# CANtranslator.net
KiCad netlist of a schematic drawn in EAGLE
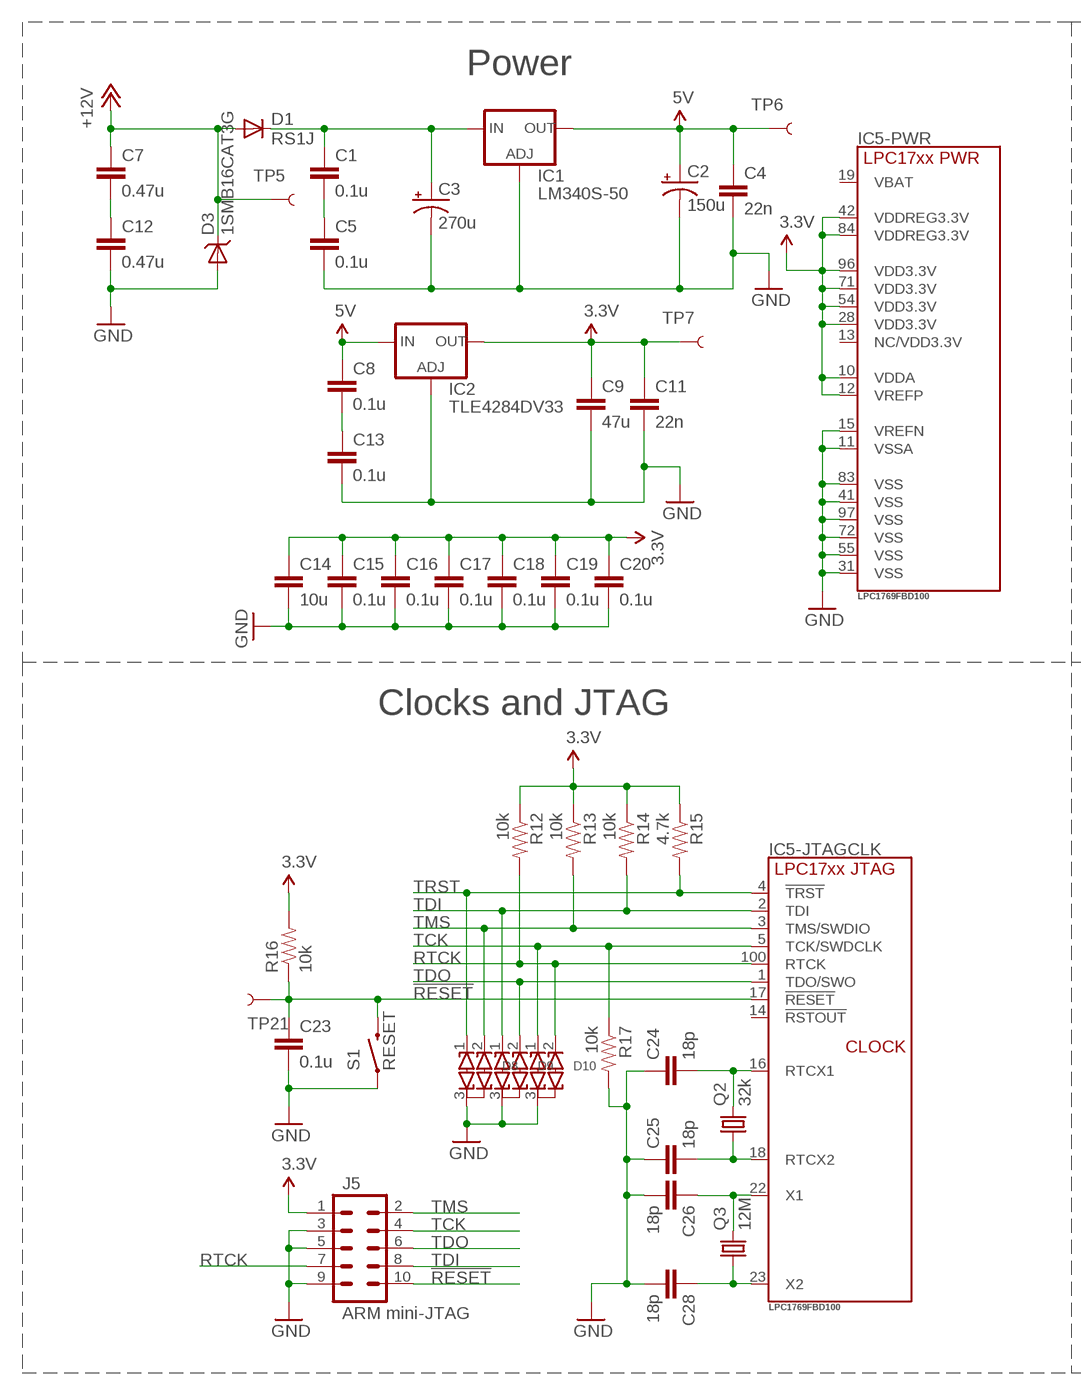
[diagram p0: schematic, sheet 1, part 1 of 2]
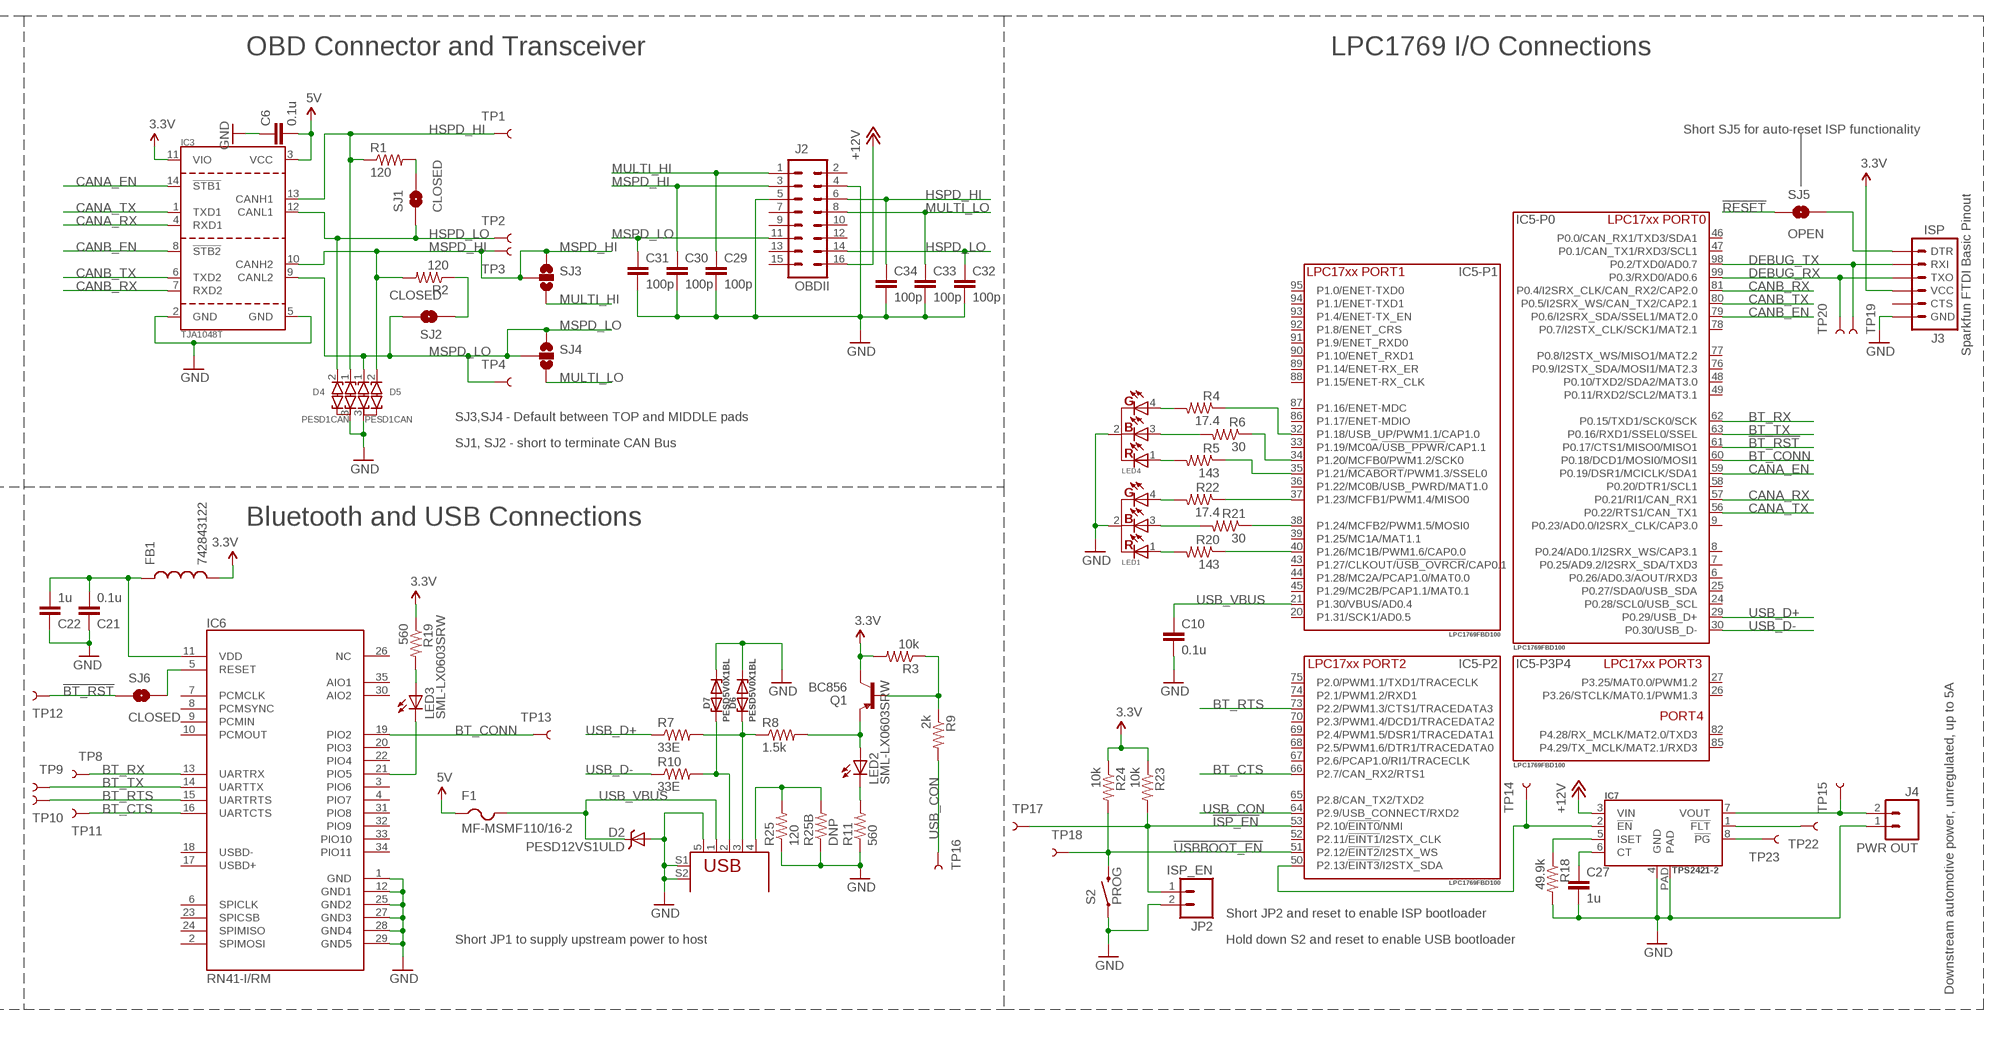
[diagram p1: schematic, sheet 1, part 2 of 2]

(export (version "E")
  (design (tool "Eeschema 10.0.6"))
  (components
    (comp (ref "C1")
      (value "0.1u")
      (footprint "eagle-import:0805")
      (libsource (lib "eagle-import") (part "CAP0805"))
    )
    (comp (ref "C2")
      (value "150u")
      (footprint "eagle-import:CPOL-5MMX2D")
      (libsource (lib "eagle-import") (part "CAP_POL5MMX2D"))
    )
    (comp (ref "C3")
      (value "270u")
      (footprint "eagle-import:CPOL-10MMX5D")
      (libsource (lib "eagle-import") (part "CAP_POL10MMX5D"))
    )
    (comp (ref "C4")
      (value "22n")
      (footprint "eagle-import:0402-CAP")
      (libsource (lib "eagle-import") (part "CAP0402-CAP"))
    )
    (comp (ref "C5")
      (value "0.1u")
      (footprint "eagle-import:0805")
      (libsource (lib "eagle-import") (part "CAP0805"))
    )
    (comp (ref "C6")
      (value "0.1u")
      (footprint "eagle-import:0402-CAP")
      (libsource (lib "eagle-import") (part "CAP0402-CAP"))
    )
    (comp (ref "C7")
      (value "0.47u")
      (footprint "eagle-import:0805")
      (libsource (lib "eagle-import") (part "CAP0805"))
    )
    (comp (ref "C8")
      (value "0.1u")
      (footprint "eagle-import:0805")
      (libsource (lib "eagle-import") (part "CAP0805"))
    )
    (comp (ref "C9")
      (value "47u")
      (footprint "eagle-import:1210")
      (libsource (lib "eagle-import") (part "CAP1210"))
    )
    (comp (ref "C10")
      (value "0.1u")
      (footprint "eagle-import:0402-CAP")
      (libsource (lib "eagle-import") (part "CAP0402-CAP"))
    )
    (comp (ref "C11")
      (value "22n")
      (footprint "eagle-import:0402-CAP")
      (libsource (lib "eagle-import") (part "CAP0402-CAP"))
    )
    (comp (ref "C12")
      (value "0.47u")
      (footprint "eagle-import:0805")
      (libsource (lib "eagle-import") (part "CAP0805"))
    )
    (comp (ref "C13")
      (value "0.1u")
      (footprint "eagle-import:0805")
      (libsource (lib "eagle-import") (part "CAP0805"))
    )
    (comp (ref "C14")
      (value "10u")
      (footprint "eagle-import:0805")
      (libsource (lib "eagle-import") (part "CAP0805"))
    )
    (comp (ref "C15")
      (value "0.1u")
      (footprint "eagle-import:0402-CAP")
      (libsource (lib "eagle-import") (part "CAP0402-CAP"))
    )
    (comp (ref "C16")
      (value "0.1u")
      (footprint "eagle-import:0402-CAP")
      (libsource (lib "eagle-import") (part "CAP0402-CAP"))
    )
    (comp (ref "C17")
      (value "0.1u")
      (footprint "eagle-import:0402-CAP")
      (libsource (lib "eagle-import") (part "CAP0402-CAP"))
    )
    (comp (ref "C18")
      (value "0.1u")
      (footprint "eagle-import:0402-CAP")
      (libsource (lib "eagle-import") (part "CAP0402-CAP"))
    )
    (comp (ref "C19")
      (value "0.1u")
      (footprint "eagle-import:0402-CAP")
      (libsource (lib "eagle-import") (part "CAP0402-CAP"))
    )
    (comp (ref "C20")
      (value "0.1u")
      (footprint "eagle-import:0402-CAP")
      (libsource (lib "eagle-import") (part "CAP0402-CAP"))
    )
    (comp (ref "C21")
      (value "0.1u")
      (footprint "eagle-import:0402-CAP")
      (libsource (lib "eagle-import") (part "CAP0402-CAP"))
    )
    (comp (ref "C22")
      (value "1u")
      (footprint "eagle-import:0402-CAP")
      (libsource (lib "eagle-import") (part "CAP0402-CAP"))
    )
    (comp (ref "C23")
      (value "0.1u")
      (footprint "eagle-import:0402-CAP")
      (libsource (lib "eagle-import") (part "CAP0402-CAP"))
    )
    (comp (ref "C24")
      (value "18p")
      (footprint "eagle-import:0402-CAP")
      (libsource (lib "eagle-import") (part "CAP0402-CAP"))
    )
    (comp (ref "C25")
      (value "18p")
      (footprint "eagle-import:0402-CAP")
      (libsource (lib "eagle-import") (part "CAP0402-CAP"))
    )
    (comp (ref "C26")
      (value "18p")
      (footprint "eagle-import:0402-CAP")
      (libsource (lib "eagle-import") (part "CAP0402-CAP"))
    )
    (comp (ref "C27")
      (value "1u")
      (footprint "eagle-import:0402-CAP")
      (libsource (lib "eagle-import") (part "CAP0402-CAP"))
    )
    (comp (ref "C28")
      (value "18p")
      (footprint "eagle-import:0402-CAP")
      (libsource (lib "eagle-import") (part "CAP0402-CAP"))
    )
    (comp (ref "C29")
      (value "100p")
      (footprint "eagle-import:0402-CAP")
      (libsource (lib "eagle-import") (part "CAP0402-CAP"))
    )
    (comp (ref "C30")
      (value "100p")
      (footprint "eagle-import:0402-CAP")
      (libsource (lib "eagle-import") (part "CAP0402-CAP"))
    )
    (comp (ref "C31")
      (value "100p")
      (footprint "eagle-import:0402-CAP")
      (libsource (lib "eagle-import") (part "CAP0402-CAP"))
    )
    (comp (ref "C32")
      (value "100p")
      (footprint "eagle-import:0402-CAP")
      (libsource (lib "eagle-import") (part "CAP0402-CAP"))
    )
    (comp (ref "C33")
      (value "100p")
      (footprint "eagle-import:0402-CAP")
      (libsource (lib "eagle-import") (part "CAP0402-CAP"))
    )
    (comp (ref "C34")
      (value "100p")
      (footprint "eagle-import:0402-CAP")
      (libsource (lib "eagle-import") (part "CAP0402-CAP"))
    )
    (comp (ref "D1")
      (value "RS1J")
      (footprint "eagle-import:SMA-DIODE")
      (libsource (lib "eagle-import") (part "DIODESMA"))
    )
    (comp (ref "D2")
      (value "PESD12VS1ULD")
      (footprint "eagle-import:SOD-882D")
      (libsource (lib "eagle-import") (part "DIODE-TVS-SOD882D"))
    )
    (comp (ref "D3")
      (value "1SMB16CAT3G")
      (footprint "eagle-import:SMB-DIODE")
      (libsource (lib "eagle-import") (part "DIODE-TVS-SMB"))
    )
    (comp (ref "D4")
      (value "PESD1CAN")
      (footprint "eagle-import:SOT23")
      (libsource (lib "eagle-import") (part "DIODE_ESD_DUAL-SOT-23"))
    )
    (comp (ref "D5")
      (value "PESD1CAN")
      (footprint "eagle-import:SOT23")
      (libsource (lib "eagle-import") (part "DIODE_ESD_DUAL-SOT-23"))
    )
    (comp (ref "D6")
      (value "PESD5V0X1BL")
      (footprint "eagle-import:SOD-882")
      (libsource (lib "eagle-import") (part "DIODE_ESD_BI-SOD882"))
    )
    (comp (ref "D7")
      (value "PESD5V0X1BL")
      (footprint "eagle-import:SOD-882")
      (libsource (lib "eagle-import") (part "DIODE_ESD_BI-SOD882"))
    )
    (comp (ref "D8")
      (value "DIODE_ESD_DUAL-SOT-1123")
      (footprint "eagle-import:SOT-1123")
      (libsource (lib "eagle-import") (part "DIODE_ESD_DUAL-SOT-1123"))
    )
    (comp (ref "D9")
      (value "DIODE_ESD_DUAL-SOT-1123")
      (footprint "eagle-import:SOT-1123")
      (libsource (lib "eagle-import") (part "DIODE_ESD_DUAL-SOT-1123"))
    )
    (comp (ref "D10")
      (value "DIODE_ESD_DUAL-SOT-1123")
      (footprint "eagle-import:SOT-1123")
      (libsource (lib "eagle-import") (part "DIODE_ESD_DUAL-SOT-1123"))
    )
    (comp (ref "F1")
      (value "MF-MSMF110/16-2")
      (footprint "eagle-import:R1206")
      (libsource (lib "eagle-import") (part "PTCFUSE-1206"))
    )
    (comp (ref "FB1")
      (value "742843122")
      (footprint "eagle-import:C0402")
      (libsource (lib "eagle-import") (part "INDUCTOR0402"))
    )
    (comp (ref "IC1")
      (value "LM340S-50")
      (footprint "eagle-import:V-REG_DPACK")
      (libsource (lib "eagle-import") (part "V_REG_317DPACK"))
    )
    (comp (ref "IC2")
      (value "TLE4284DV33")
      (footprint "eagle-import:V-REG_DPACK")
      (libsource (lib "eagle-import") (part "V_REG_317DPACK"))
    )
    (comp (ref "IC3")
      (value "TJA1048T")
      (footprint "eagle-import:SO14")
      (libsource (lib "eagle-import") (part "TJA1048-SO14"))
    )
    (comp (ref "IC5")
      (value "LPC1769FBD100")
      (footprint "eagle-import:TQFP100")
      (libsource (lib "eagle-import") (part "LPC1768_SPLIT-TQFP"))
    )
    (comp (ref "IC6")
      (value "RN41-I/RM")
      (footprint "eagle-import:RN41")
      (libsource (lib "eagle-import") (part "BLUETOOTH-RN41{dblquote}"))
    )
    (comp (ref "IC7")
      (value "TPS2421-2")
      (footprint "eagle-import:POWER_SO8")
      (libsource (lib "eagle-import") (part "TPS2421SO8"))
    )
    (comp (ref "J1")
      (value "USB_MINIB_SHIELD-10118193")
      (footprint "eagle-import:10118193")
      (libsource (lib "eagle-import") (part "USB_MINIB_SHIELD-10118193"))
    )
    (comp (ref "J2")
      (value "OBDII")
      (footprint "eagle-import:OBDII-COMTECH")
      (libsource (lib "eagle-import") (part "M08X2-OBDII-COMTECH"))
    )
    (comp (ref "J3")
      (value "ISP")
      (footprint "eagle-import:1X06")
      (libsource (lib "eagle-import") (part "ARDUINO_SERIAL_PROGRAMPTH"))
    )
    (comp (ref "J4")
      (value "PWR OUT")
      (footprint "eagle-import:2-1445055-2")
      (libsource (lib "eagle-import") (part "M022-1445055-2"))
    )
    (comp (ref "J5")
      (value "ARM mini-JTAG")
      (footprint "eagle-import:SHF-105-01-X-D-SM")
      (libsource (lib "eagle-import") (part "M05X2-SHF-105-01-X-D-SM"))
    )
    (comp (ref "JP2")
      (value "ISP_EN")
      (footprint "eagle-import:1X02")
      (libsource (lib "eagle-import") (part "SparkFun-Connectors_M02PTH"))
    )
    (comp (ref "LED1")
      (value "RGB")
      (footprint "eagle-import:LED5MM-RGB")
      (libsource (lib "eagle-import") (part "LED_3X_COMMON_CATHODE"))
    )
    (comp (ref "LED2")
      (value "SML-LX0603SRW")
      (footprint "eagle-import:LED-0603")
      (libsource (lib "eagle-import") (part "LED0603"))
    )
    (comp (ref "LED3")
      (value "SML-LX0603SRW")
      (footprint "eagle-import:LED-0603")
      (libsource (lib "eagle-import") (part "LED0603"))
    )
    (comp (ref "LED4")
      (value "RGB")
      (footprint "eagle-import:LED5MM-RGB")
      (libsource (lib "eagle-import") (part "LED_3X_COMMON_CATHODE"))
    )
    (comp (ref "Q1")
      (value "BC856")
      (footprint "eagle-import:SOT23-3")
      (libsource (lib "eagle-import") (part "TRANSISTOR_PNPSMD"))
    )
    (comp (ref "Q2")
      (value "32k")
      (footprint "eagle-import:ST2012SB")
      (libsource (lib "eagle-import") (part "CRYSTAL-ST2012SB"))
    )
    (comp (ref "Q3")
      (value "12M")
      (footprint "eagle-import:CX3225SB")
      (libsource (lib "eagle-import") (part "CRYSTAL-CX3225SB"))
    )
    (comp (ref "R1")
      (value "120")
      (footprint "eagle-import:0402-RES")
      (libsource (lib "eagle-import") (part "RESISTOR0402-RES"))
    )
    (comp (ref "R2")
      (value "120")
      (footprint "eagle-import:0402-RES")
      (libsource (lib "eagle-import") (part "RESISTOR0402-RES"))
    )
    (comp (ref "R3")
      (value "10k")
      (footprint "eagle-import:0402-RES")
      (libsource (lib "eagle-import") (part "RESISTOR0402-RES"))
    )
    (comp (ref "R4")
      (value "17.4")
      (footprint "eagle-import:0402-RES")
      (libsource (lib "eagle-import") (part "RESISTOR0402-RES"))
    )
    (comp (ref "R5")
      (value "143")
      (footprint "eagle-import:0402-RES")
      (libsource (lib "eagle-import") (part "RESISTOR0402-RES"))
    )
    (comp (ref "R6")
      (value "30")
      (footprint "eagle-import:0402-RES")
      (libsource (lib "eagle-import") (part "RESISTOR0402-RES"))
    )
    (comp (ref "R7")
      (value "33E")
      (footprint "eagle-import:0402-RES")
      (libsource (lib "eagle-import") (part "RESISTOR0402-RES"))
    )
    (comp (ref "R8")
      (value "1.5k")
      (footprint "eagle-import:0402-RES")
      (libsource (lib "eagle-import") (part "RESISTOR0402-RES"))
    )
    (comp (ref "R9")
      (value "2k")
      (footprint "eagle-import:0402-RES")
      (libsource (lib "eagle-import") (part "RESISTOR0402-RES"))
    )
    (comp (ref "R10")
      (value "33E")
      (footprint "eagle-import:0402-RES")
      (libsource (lib "eagle-import") (part "RESISTOR0402-RES"))
    )
    (comp (ref "R11")
      (value "560")
      (footprint "eagle-import:0402-RES")
      (libsource (lib "eagle-import") (part "RESISTOR0402-RES"))
    )
    (comp (ref "R12")
      (value "10k")
      (footprint "eagle-import:0402-RES")
      (libsource (lib "eagle-import") (part "RESISTOR0402-RES"))
    )
    (comp (ref "R13")
      (value "10k")
      (footprint "eagle-import:0402-RES")
      (libsource (lib "eagle-import") (part "RESISTOR0402-RES"))
    )
    (comp (ref "R14")
      (value "10k")
      (footprint "eagle-import:0402-RES")
      (libsource (lib "eagle-import") (part "RESISTOR0402-RES"))
    )
    (comp (ref "R15")
      (value "4.7k")
      (footprint "eagle-import:0402-RES")
      (libsource (lib "eagle-import") (part "RESISTOR0402-RES"))
    )
    (comp (ref "R16")
      (value "10k")
      (footprint "eagle-import:0402-RES")
      (libsource (lib "eagle-import") (part "RESISTOR0402-RES"))
    )
    (comp (ref "R17")
      (value "10k")
      (footprint "eagle-import:0402-RES")
      (libsource (lib "eagle-import") (part "RESISTOR0402-RES"))
    )
    (comp (ref "R18")
      (value "49.9k")
      (footprint "eagle-import:0402-RES")
      (libsource (lib "eagle-import") (part "RESISTOR0402-RES"))
    )
    (comp (ref "R19")
      (value "560")
      (footprint "eagle-import:0402-RES")
      (libsource (lib "eagle-import") (part "RESISTOR0402-RES"))
    )
    (comp (ref "R20")
      (value "143")
      (footprint "eagle-import:0402-RES")
      (libsource (lib "eagle-import") (part "RESISTOR0402-RES"))
    )
    (comp (ref "R21")
      (value "30")
      (footprint "eagle-import:0402-RES")
      (libsource (lib "eagle-import") (part "RESISTOR0402-RES"))
    )
    (comp (ref "R22")
      (value "17.4")
      (footprint "eagle-import:0402-RES")
      (libsource (lib "eagle-import") (part "RESISTOR0402-RES"))
    )
    (comp (ref "R23")
      (value "10k")
      (footprint "eagle-import:0402-RES")
      (libsource (lib "eagle-import") (part "RESISTOR0402-RES"))
    )
    (comp (ref "R24")
      (value "10k")
      (footprint "eagle-import:0402-RES")
      (libsource (lib "eagle-import") (part "RESISTOR0402-RES"))
    )
    (comp (ref "R25")
      (value "120")
      (footprint "eagle-import:0402-RES")
      (libsource (lib "eagle-import") (part "RESISTOR0402-RES"))
    )
    (comp (ref "R25B")
      (value "DNP")
      (footprint "eagle-import:AXIAL-0.4")
      (libsource (lib "eagle-import") (part "RESISTORPTH-1/4W"))
    )
    (comp (ref "S1")
      (value "RESET")
      (footprint "eagle-import:TACTILE-SWITCH-1101NE")
      (libsource (lib "eagle-import") (part "SWITCH-MOMENTARY-2-SMD-1101NE"))
    )
    (comp (ref "S2")
      (value "PROG")
      (footprint "eagle-import:TACTILE-SWITCH-1101NE")
      (libsource (lib "eagle-import") (part "SWITCH-MOMENTARY-2-SMD-1101NE"))
    )
    (comp (ref "SJ1")
      (value "CLOSED")
      (footprint "eagle-import:SJ_2S-TRACE")
      (libsource (lib "eagle-import") (part "SOLDERJUMPERTRACE"))
    )
    (comp (ref "SJ2")
      (value "CLOSED")
      (footprint "eagle-import:SJ_2S-TRACE")
      (libsource (lib "eagle-import") (part "SOLDERJUMPERTRACE"))
    )
    (comp (ref "SJ3")
      (value "SOLDERJUMPER_2WAYPASTE1&2")
      (footprint "eagle-import:SJ_3_PASTE1&2")
      (libsource (lib "eagle-import") (part "SOLDERJUMPER_2WAYPASTE1&2"))
    )
    (comp (ref "SJ4")
      (value "SOLDERJUMPER_2WAYPASTE1&2")
      (footprint "eagle-import:SJ_3_PASTE1&2")
      (libsource (lib "eagle-import") (part "SOLDERJUMPER_2WAYPASTE1&2"))
    )
    (comp (ref "SJ5")
      (value "OPEN")
      (footprint "eagle-import:SJ_2S-NO")
      (libsource (lib "eagle-import") (part "SOLDERJUMPERNO"))
    )
    (comp (ref "SJ6")
      (value "CLOSED")
      (footprint "eagle-import:SJ_2S-TRACE")
      (libsource (lib "eagle-import") (part "SOLDERJUMPERTRACE"))
    )
    (comp (ref "TP1")
      (value "TEST-POINT3X5")
      (footprint "eagle-import:PAD.03X.05")
      (libsource (lib "eagle-import") (part "TEST-POINT3X5"))
    )
    (comp (ref "TP2")
      (value "TEST-POINT3X5")
      (footprint "eagle-import:PAD.03X.05")
      (libsource (lib "eagle-import") (part "TEST-POINT3X5"))
    )
    (comp (ref "TP3")
      (value "TEST-POINT3X5")
      (footprint "eagle-import:PAD.03X.05")
      (libsource (lib "eagle-import") (part "TEST-POINT3X5"))
    )
    (comp (ref "TP4")
      (value "TEST-POINT3X5")
      (footprint "eagle-import:PAD.03X.05")
      (libsource (lib "eagle-import") (part "TEST-POINT3X5"))
    )
    (comp (ref "TP5")
      (value "TEST-POINT3X5")
      (footprint "eagle-import:PAD.03X.05")
      (libsource (lib "eagle-import") (part "TEST-POINT3X5"))
    )
    (comp (ref "TP6")
      (value "TEST-POINT3X5")
      (footprint "eagle-import:PAD.03X.05")
      (libsource (lib "eagle-import") (part "TEST-POINT3X5"))
    )
    (comp (ref "TP7")
      (value "TEST-POINT3X5")
      (footprint "eagle-import:PAD.03X.05")
      (libsource (lib "eagle-import") (part "TEST-POINT3X5"))
    )
    (comp (ref "TP8")
      (value "TEST-POINT3X5")
      (footprint "eagle-import:PAD.03X.05")
      (libsource (lib "eagle-import") (part "TEST-POINT3X5"))
    )
    (comp (ref "TP9")
      (value "TEST-POINT3X5")
      (footprint "eagle-import:PAD.03X.05")
      (libsource (lib "eagle-import") (part "TEST-POINT3X5"))
    )
    (comp (ref "TP10")
      (value "TEST-POINT3X5")
      (footprint "eagle-import:PAD.03X.05")
      (libsource (lib "eagle-import") (part "TEST-POINT3X5"))
    )
    (comp (ref "TP11")
      (value "TEST-POINT3X5")
      (footprint "eagle-import:PAD.03X.05")
      (libsource (lib "eagle-import") (part "TEST-POINT3X5"))
    )
    (comp (ref "TP12")
      (value "TEST-POINT3X5")
      (footprint "eagle-import:PAD.03X.05")
      (libsource (lib "eagle-import") (part "TEST-POINT3X5"))
    )
    (comp (ref "TP13")
      (value "TEST-POINT3X5")
      (footprint "eagle-import:PAD.03X.05")
      (libsource (lib "eagle-import") (part "TEST-POINT3X5"))
    )
    (comp (ref "TP14")
      (value "TEST-POINT3X5")
      (footprint "eagle-import:PAD.03X.05")
      (libsource (lib "eagle-import") (part "TEST-POINT3X5"))
    )
    (comp (ref "TP15")
      (value "TEST-POINT3X5")
      (footprint "eagle-import:PAD.03X.05")
      (libsource (lib "eagle-import") (part "TEST-POINT3X5"))
    )
    (comp (ref "TP16")
      (value "TEST-POINT3X5")
      (footprint "eagle-import:PAD.03X.05")
      (libsource (lib "eagle-import") (part "TEST-POINT3X5"))
    )
    (comp (ref "TP17")
      (value "TEST-POINT3X5")
      (footprint "eagle-import:PAD.03X.05")
      (libsource (lib "eagle-import") (part "TEST-POINT3X5"))
    )
    (comp (ref "TP18")
      (value "TEST-POINT3X5")
      (footprint "eagle-import:PAD.03X.05")
      (libsource (lib "eagle-import") (part "TEST-POINT3X5"))
    )
    (comp (ref "TP19")
      (value "TEST-POINT3X5")
      (footprint "eagle-import:PAD.03X.05")
      (libsource (lib "eagle-import") (part "TEST-POINT3X5"))
    )
    (comp (ref "TP20")
      (value "TEST-POINT3X5")
      (footprint "eagle-import:PAD.03X.05")
      (libsource (lib "eagle-import") (part "TEST-POINT3X5"))
    )
    (comp (ref "TP21")
      (value "TEST-POINT3X5")
      (footprint "eagle-import:PAD.03X.05")
      (libsource (lib "eagle-import") (part "TEST-POINT3X5"))
    )
    (comp (ref "TP22")
      (value "TEST-POINT3X5")
      (footprint "eagle-import:PAD.03X.05")
      (libsource (lib "eagle-import") (part "TEST-POINT3X5"))
    )
    (comp (ref "TP23")
      (value "TEST-POINT3X5")
      (footprint "eagle-import:PAD.03X.05")
      (libsource (lib "eagle-import") (part "TEST-POINT3X5"))
    )
  )
  (nets
    (net (code "1") (name "+12V") (class "Default")
      (node (ref "C7") (pin "1") (pinfunction "1_1") (pintype "passive"))
      (node (ref "D1") (pin "A") (pinfunction "A_A") (pintype "passive"))
      (node (ref "D3") (pin "C") (pinfunction "C_C") (pintype "passive"))
      (node (ref "IC7") (pin "3") (pinfunction "VIN_3") (pintype "bidirectional"))
      (node (ref "J2") (pin "16") (pinfunction "16_16") (pintype "passive"))
      (node (ref "TP5") (pin "P$1") (pinfunction "1_P$1") (pintype "bidirectional"))
    )
    (net (code "2") (name "/BT_CONN") (class "Default")
      (node (ref "IC5") (pin "60") (pinfunction "P0.18/DCD1/MOSI0/MOSI1_60") (pintype "bidirectional"))
      (node (ref "IC6") (pin "19") (pinfunction "PIO2_19") (pintype "bidirectional"))
      (node (ref "TP13") (pin "P$1") (pinfunction "1_P$1") (pintype "bidirectional"))
    )
    (net (code "3") (name "/BT_CTS") (class "Default")
      (node (ref "IC5") (pin "66") (pinfunction "P2.7/CAN_RX2/RTS1_66") (pintype "bidirectional"))
      (node (ref "IC6") (pin "16") (pinfunction "UARTCTS_16") (pintype "bidirectional"))
      (node (ref "TP11") (pin "P$1") (pinfunction "1_P$1") (pintype "bidirectional"))
    )
    (net (code "4") (name "/BT_RTS") (class "Default")
      (node (ref "IC5") (pin "73") (pinfunction "P2.2/PWM1.3/CTS1/TRACEDATA3_73") (pintype "bidirectional"))
      (node (ref "IC6") (pin "15") (pinfunction "UARTRTS_15") (pintype "bidirectional"))
      (node (ref "TP10") (pin "P$1") (pinfunction "1_P$1") (pintype "bidirectional"))
    )
    (net (code "5") (name "/BT_RX") (class "Default")
      (node (ref "IC5") (pin "62") (pinfunction "P0.15/TXD1/SCK0/SCK_62") (pintype "bidirectional"))
      (node (ref "IC6") (pin "13") (pinfunction "UARTRX_13") (pintype "bidirectional"))
      (node (ref "TP8") (pin "P$1") (pinfunction "1_P$1") (pintype "bidirectional"))
    )
    (net (code "6") (name "/BT_TX") (class "Default")
      (node (ref "IC5") (pin "63") (pinfunction "P0.16/RXD1/SSEL0/SSEL_63") (pintype "bidirectional"))
      (node (ref "IC6") (pin "14") (pinfunction "UARTTX_14") (pintype "bidirectional"))
      (node (ref "TP9") (pin "P$1") (pinfunction "1_P$1") (pintype "bidirectional"))
    )
    (net (code "7") (name "/CANA_EN") (class "Default")
      (node (ref "IC3") (pin "14") (pinfunction "~{STB1}_14") (pintype "bidirectional"))
      (node (ref "IC5") (pin "59") (pinfunction "P0.19/DSR1/MCICLK/SDA1_59") (pintype "bidirectional"))
    )
    (net (code "8") (name "/CANA_RX") (class "Default")
      (node (ref "IC3") (pin "4") (pinfunction "RXD1_4") (pintype "bidirectional"))
      (node (ref "IC5") (pin "57") (pinfunction "P0.21/RI1/CAN_RX1_57") (pintype "bidirectional"))
    )
    (net (code "9") (name "/CANA_TX") (class "Default")
      (node (ref "IC3") (pin "1") (pinfunction "TXD1_1") (pintype "bidirectional"))
      (node (ref "IC5") (pin "56") (pinfunction "P0.22/RTS1/CAN_TX1_56") (pintype "bidirectional"))
    )
    (net (code "10") (name "/CANB_EN") (class "Default")
      (node (ref "IC3") (pin "8") (pinfunction "~{STB2}_8") (pintype "bidirectional"))
      (node (ref "IC5") (pin "79") (pinfunction "P0.6/I2SRX_SDA/SSEL1/MAT2.0_79") (pintype "bidirectional"))
    )
    (net (code "11") (name "/CANB_RX") (class "Default")
      (node (ref "IC3") (pin "7") (pinfunction "RXD2_7") (pintype "bidirectional"))
      (node (ref "IC5") (pin "81") (pinfunction "P0.4/I2SRX_CLK/CAN_RX2/CAP2.0_81") (pintype "bidirectional"))
    )
    (net (code "12") (name "/CANB_TX") (class "Default")
      (node (ref "IC3") (pin "6") (pinfunction "TXD2_6") (pintype "bidirectional"))
      (node (ref "IC5") (pin "80") (pinfunction "P0.5/I2SRX_WS/CAN_TX2/CAP2.1_80") (pintype "bidirectional"))
    )
    (net (code "13") (name "/DEBUG_RX") (class "Default")
      (node (ref "IC5") (pin "99") (pinfunction "P0.3/RXD0/AD0.6_99") (pintype "bidirectional"))
      (node (ref "J3") (pin "3") (pinfunction "TXO_3") (pintype "passive"))
      (node (ref "TP20") (pin "P$1") (pinfunction "1_P$1") (pintype "bidirectional"))
    )
    (net (code "14") (name "/DEBUG_TX") (class "Default")
      (node (ref "IC5") (pin "98") (pinfunction "P0.2/TXD0/AD0.7_98") (pintype "bidirectional"))
      (node (ref "J3") (pin "2") (pinfunction "RXI_2") (pintype "passive"))
      (node (ref "TP19") (pin "P$1") (pinfunction "1_P$1") (pintype "bidirectional"))
    )
    (net (code "15") (name "/HSPD_HI") (class "Default")
      (node (ref "C34") (pin "1") (pinfunction "1_1") (pintype "passive"))
      (node (ref "D4") (pin "1") (pinfunction "C1_1") (pintype "power_in"))
      (node (ref "IC3") (pin "13") (pinfunction "CANH1_13") (pintype "bidirectional"))
      (node (ref "J2") (pin "6") (pinfunction "6_6") (pintype "passive"))
      (node (ref "R1") (pin "1") (pinfunction "1_1") (pintype "passive"))
      (node (ref "TP1") (pin "P$1") (pinfunction "1_P$1") (pintype "bidirectional"))
    )
    (net (code "16") (name "/HSPD_LO") (class "Default")
      (node (ref "C32") (pin "1") (pinfunction "1_1") (pintype "passive"))
      (node (ref "D4") (pin "2") (pinfunction "C2_2") (pintype "power_in"))
      (node (ref "IC3") (pin "12") (pinfunction "CANL1_12") (pintype "bidirectional"))
      (node (ref "J2") (pin "14") (pinfunction "14_14") (pintype "passive"))
      (node (ref "SJ1") (pin "1") (pinfunction "1_1") (pintype "passive"))
      (node (ref "TP2") (pin "P$1") (pinfunction "1_P$1") (pintype "bidirectional"))
    )
    (net (code "17") (name "/MSPD_HI") (class "Default")
      (node (ref "C30") (pin "1") (pinfunction "1_1") (pintype "passive"))
      (node (ref "D5") (pin "2") (pinfunction "C2_2") (pintype "power_in"))
      (node (ref "IC3") (pin "10") (pinfunction "CANH2_10") (pintype "bidirectional"))
      (node (ref "J2") (pin "3") (pinfunction "3_3") (pintype "passive"))
      (node (ref "R2") (pin "2") (pinfunction "2_2") (pintype "passive"))
      (node (ref "SJ3") (pin "1") (pinfunction "1_1") (pintype "passive"))
      (node (ref "SJ3") (pin "2") (pinfunction "2_2") (pintype "passive"))
      (node (ref "TP3") (pin "P$1") (pinfunction "1_P$1") (pintype "bidirectional"))
    )
    (net (code "18") (name "/MSPD_LO") (class "Default")
      (node (ref "C31") (pin "1") (pinfunction "1_1") (pintype "passive"))
      (node (ref "D5") (pin "1") (pinfunction "C1_1") (pintype "power_in"))
      (node (ref "IC3") (pin "9") (pinfunction "CANL2_9") (pintype "bidirectional"))
      (node (ref "J2") (pin "11") (pinfunction "11_11") (pintype "passive"))
      (node (ref "SJ2") (pin "2") (pinfunction "2_2") (pintype "passive"))
      (node (ref "SJ4") (pin "1") (pinfunction "1_1") (pintype "passive"))
      (node (ref "SJ4") (pin "2") (pinfunction "2_2") (pintype "passive"))
      (node (ref "TP4") (pin "P$1") (pinfunction "1_P$1") (pintype "bidirectional"))
    )
    (net (code "19") (name "/MULTI_HI") (class "Default")
      (node (ref "C29") (pin "1") (pinfunction "1_1") (pintype "passive"))
      (node (ref "J2") (pin "1") (pinfunction "1_1") (pintype "passive"))
      (node (ref "SJ3") (pin "3") (pinfunction "3_3") (pintype "passive"))
    )
    (net (code "20") (name "/MULTI_LO") (class "Default")
      (node (ref "C33") (pin "1") (pinfunction "1_1") (pintype "passive"))
      (node (ref "J2") (pin "8") (pinfunction "8_8") (pintype "passive"))
      (node (ref "SJ4") (pin "3") (pinfunction "3_3") (pintype "passive"))
    )
    (net (code "21") (name "/RTCK") (class "Default")
      (node (ref "D10") (pin "2") (pinfunction "C2_2") (pintype "power_in"))
      (node (ref "IC5") (pin "100") (pinfunction "RTCK_100") (pintype "bidirectional"))
      (node (ref "J5") (pin "7") (pinfunction "7_7") (pintype "passive"))
      (node (ref "R12") (pin "2") (pinfunction "2_2") (pintype "passive"))
    )
    (net (code "22") (name "/TCK") (class "Default")
      (node (ref "D10") (pin "1") (pinfunction "C1_1") (pintype "power_in"))
      (node (ref "IC5") (pin "5") (pinfunction "TCK/SWDCLK_5") (pintype "bidirectional"))
      (node (ref "J5") (pin "4") (pinfunction "4_4") (pintype "passive"))
      (node (ref "R17") (pin "1") (pinfunction "1_1") (pintype "passive"))
    )
    (net (code "23") (name "/TDI") (class "Default")
      (node (ref "D9") (pin "1") (pinfunction "C1_1") (pintype "power_in"))
      (node (ref "IC5") (pin "2") (pinfunction "TDI_2") (pintype "bidirectional"))
      (node (ref "J5") (pin "8") (pinfunction "8_8") (pintype "passive"))
      (node (ref "R14") (pin "2") (pinfunction "2_2") (pintype "passive"))
    )
    (net (code "24") (name "/TDO") (class "Default")
      (node (ref "D9") (pin "2") (pinfunction "C2_2") (pintype "power_in"))
      (node (ref "IC5") (pin "1") (pinfunction "TDO/SWO_1") (pintype "bidirectional"))
      (node (ref "J5") (pin "6") (pinfunction "6_6") (pintype "passive"))
    )
    (net (code "25") (name "/TMS") (class "Default")
      (node (ref "D8") (pin "2") (pinfunction "C2_2") (pintype "power_in"))
      (node (ref "IC5") (pin "3") (pinfunction "TMS/SWDIO_3") (pintype "bidirectional"))
      (node (ref "J5") (pin "2") (pinfunction "2_2") (pintype "passive"))
      (node (ref "R13") (pin "2") (pinfunction "2_2") (pintype "passive"))
    )
    (net (code "26") (name "/TRST") (class "Default")
      (node (ref "D8") (pin "1") (pinfunction "C1_1") (pintype "power_in"))
      (node (ref "IC5") (pin "4") (pinfunction "~{TRST}_4") (pintype "bidirectional"))
      (node (ref "R15") (pin "2") (pinfunction "2_2") (pintype "passive"))
    )
    (net (code "27") (name "/USB_CON") (class "Default")
      (node (ref "IC5") (pin "64") (pinfunction "P2.9/USB_CONNECT/RXD2_64") (pintype "bidirectional"))
      (node (ref "R9") (pin "2") (pinfunction "2_2") (pintype "passive"))
      (node (ref "TP16") (pin "P$1") (pinfunction "1_P$1") (pintype "bidirectional"))
    )
    (net (code "28") (name "/USB_D+") (class "Default")
      (node (ref "IC5") (pin "29") (pinfunction "P0.29/USB_D+_29") (pintype "bidirectional"))
      (node (ref "R7") (pin "1") (pinfunction "1_1") (pintype "passive"))
    )
    (net (code "29") (name "/USB_D-") (class "Default")
      (node (ref "IC5") (pin "30") (pinfunction "P0.30/USB_D-_30") (pintype "bidirectional"))
      (node (ref "R10") (pin "1") (pinfunction "1_1") (pintype "passive"))
    )
    (net (code "30") (name "/USB_VBUS") (class "Default")
      (node (ref "C10") (pin "1") (pinfunction "1_1") (pintype "passive"))
      (node (ref "D2") (pin "1") (pinfunction "C_1") (pintype "passive"))
      (node (ref "F1") (pin "2") (pinfunction "2_2") (pintype "passive"))
      (node (ref "IC5") (pin "21") (pinfunction "P1.30/VBUS/AD0.4_21") (pintype "bidirectional"))
      (node (ref "J1") (pin "1") (pinfunction "VBUS_1") (pintype "bidirectional"))
    )
    (net (code "31") (name "/~{BT_RST}") (class "Default")
      (node (ref "IC5") (pin "61") (pinfunction "P0.17/CTS1/MISO0/MISO1_61") (pintype "bidirectional"))
      (node (ref "SJ6") (pin "1") (pinfunction "1_1") (pintype "passive"))
      (node (ref "TP12") (pin "P$1") (pinfunction "1_P$1") (pintype "bidirectional"))
    )
    (net (code "32") (name "/~{ISP_EN}") (class "Default")
      (node (ref "IC5") (pin "53") (pinfunction "P2.10/~{EINT0}/NMI_53") (pintype "bidirectional"))
      (node (ref "JP2") (pin "1") (pinfunction "1_1") (pintype "passive"))
      (node (ref "R23") (pin "2") (pinfunction "2_2") (pintype "passive"))
      (node (ref "TP17") (pin "P$1") (pinfunction "1_P$1") (pintype "bidirectional"))
    )
    (net (code "33") (name "/~{RESET}") (class "Default")
      (node (ref "C23") (pin "1") (pinfunction "1_1") (pintype "passive"))
      (node (ref "IC5") (pin "17") (pinfunction "~{RESET}_17") (pintype "bidirectional"))
      (node (ref "J5") (pin "10") (pinfunction "10_10") (pintype "passive"))
      (node (ref "R16") (pin "1") (pinfunction "1_1") (pintype "passive"))
      (node (ref "S1") (pin "P$2") (pinfunction "2_P$2") (pintype "passive"))
      (node (ref "SJ5") (pin "1") (pinfunction "1_1") (pintype "passive"))
      (node (ref "TP21") (pin "P$1") (pinfunction "1_P$1") (pintype "bidirectional"))
    )
    (net (code "34") (name "/~{USBBOOT_EN}") (class "Default")
      (node (ref "IC5") (pin "51") (pinfunction "P2.12/~{EINT2}/I2STX_WS_51") (pintype "bidirectional"))
      (node (ref "R24") (pin "2") (pinfunction "2_2") (pintype "passive"))
      (node (ref "S2") (pin "P$2") (pinfunction "2_P$2") (pintype "passive"))
      (node (ref "TP18") (pin "P$1") (pinfunction "1_P$1") (pintype "bidirectional"))
    )
    (net (code "35") (name "3.3V") (class "Default")
      (node (ref "C11") (pin "1") (pinfunction "1_1") (pintype "passive"))
      (node (ref "C14") (pin "1") (pinfunction "1_1") (pintype "passive"))
      (node (ref "C15") (pin "1") (pinfunction "1_1") (pintype "passive"))
      (node (ref "C16") (pin "1") (pinfunction "1_1") (pintype "passive"))
      (node (ref "C17") (pin "1") (pinfunction "1_1") (pintype "passive"))
      (node (ref "C18") (pin "1") (pinfunction "1_1") (pintype "passive"))
      (node (ref "C19") (pin "1") (pinfunction "1_1") (pintype "passive"))
      (node (ref "C20") (pin "1") (pinfunction "1_1") (pintype "passive"))
      (node (ref "C9") (pin "1") (pinfunction "1_1") (pintype "passive"))
      (node (ref "FB1") (pin "2") (pinfunction "2_2") (pintype "passive"))
      (node (ref "IC2") (pin "4") (pinfunction "OUT_4") (pintype "output"))
      (node (ref "IC3") (pin "11") (pinfunction "VIO_11") (pintype "bidirectional"))
      (node (ref "IC5") (pin "10") (pinfunction "VDDA_10") (pintype "bidirectional"))
      (node (ref "IC5") (pin "12") (pinfunction "VREFP_12") (pintype "bidirectional"))
      (node (ref "IC5") (pin "28") (pinfunction "VDD3.3V_28") (pintype "bidirectional"))
      (node (ref "IC5") (pin "42") (pinfunction "VDDREG3.3V_42") (pintype "bidirectional"))
      (node (ref "IC5") (pin "54") (pinfunction "VDD3.3V_54") (pintype "bidirectional"))
      (node (ref "IC5") (pin "71") (pinfunction "VDD3.3V_71") (pintype "bidirectional"))
      (node (ref "IC5") (pin "84") (pinfunction "VDDREG3.3V_84") (pintype "bidirectional"))
      (node (ref "IC5") (pin "96") (pinfunction "VDD3.3V_96") (pintype "bidirectional"))
      (node (ref "J3") (pin "4") (pinfunction "VCC_4") (pintype "passive"))
      (node (ref "J5") (pin "1") (pinfunction "1_1") (pintype "passive"))
      (node (ref "Q1") (pin "3") (pinfunction "C_3") (pintype "passive"))
      (node (ref "R12") (pin "1") (pinfunction "1_1") (pintype "passive"))
      (node (ref "R13") (pin "1") (pinfunction "1_1") (pintype "passive"))
      (node (ref "R14") (pin "1") (pinfunction "1_1") (pintype "passive"))
      (node (ref "R15") (pin "1") (pinfunction "1_1") (pintype "passive"))
      (node (ref "R16") (pin "2") (pinfunction "2_2") (pintype "passive"))
      (node (ref "R19") (pin "1") (pinfunction "1_1") (pintype "passive"))
      (node (ref "R23") (pin "1") (pinfunction "1_1") (pintype "passive"))
      (node (ref "R24") (pin "1") (pinfunction "1_1") (pintype "passive"))
      (node (ref "R3") (pin "2") (pinfunction "2_2") (pintype "passive"))
      (node (ref "TP7") (pin "P$1") (pinfunction "1_P$1") (pintype "bidirectional"))
    )
    (net (code "36") (name "5V") (class "Default")
      (node (ref "C2") (pin "1") (pinfunction "+_1") (pintype "passive"))
      (node (ref "C4") (pin "1") (pinfunction "1_1") (pintype "passive"))
      (node (ref "C6") (pin "2") (pinfunction "2_2") (pintype "passive"))
      (node (ref "C8") (pin "1") (pinfunction "1_1") (pintype "passive"))
      (node (ref "F1") (pin "1") (pinfunction "1_1") (pintype "passive"))
      (node (ref "IC1") (pin "4") (pinfunction "OUT_4") (pintype "output"))
      (node (ref "IC2") (pin "3") (pinfunction "IN_3") (pintype "input"))
      (node (ref "IC3") (pin "3") (pinfunction "VCC_3") (pintype "bidirectional"))
      (node (ref "TP6") (pin "P$1") (pinfunction "1_P$1") (pintype "bidirectional"))
    )
    (net (code "37") (name "GND") (class "Default")
      (node (ref "C10") (pin "2") (pinfunction "2_2") (pintype "passive"))
      (node (ref "C11") (pin "2") (pinfunction "2_2") (pintype "passive"))
      (node (ref "C12") (pin "2") (pinfunction "2_2") (pintype "passive"))
      (node (ref "C13") (pin "2") (pinfunction "2_2") (pintype "passive"))
      (node (ref "C14") (pin "2") (pinfunction "2_2") (pintype "passive"))
      (node (ref "C15") (pin "2") (pinfunction "2_2") (pintype "passive"))
      (node (ref "C16") (pin "2") (pinfunction "2_2") (pintype "passive"))
      (node (ref "C17") (pin "2") (pinfunction "2_2") (pintype "passive"))
      (node (ref "C18") (pin "2") (pinfunction "2_2") (pintype "passive"))
      (node (ref "C19") (pin "2") (pinfunction "2_2") (pintype "passive"))
      (node (ref "C2") (pin "2") (pinfunction "-_2") (pintype "passive"))
      (node (ref "C20") (pin "2") (pinfunction "2_2") (pintype "passive"))
      (node (ref "C21") (pin "1") (pinfunction "1_1") (pintype "passive"))
      (node (ref "C22") (pin "1") (pinfunction "1_1") (pintype "passive"))
      (node (ref "C23") (pin "2") (pinfunction "2_2") (pintype "passive"))
      (node (ref "C24") (pin "1") (pinfunction "1_1") (pintype "passive"))
      (node (ref "C25") (pin "1") (pinfunction "1_1") (pintype "passive"))
      (node (ref "C26") (pin "2") (pinfunction "2_2") (pintype "passive"))
      (node (ref "C27") (pin "2") (pinfunction "2_2") (pintype "passive"))
      (node (ref "C28") (pin "2") (pinfunction "2_2") (pintype "passive"))
      (node (ref "C29") (pin "2") (pinfunction "2_2") (pintype "passive"))
      (node (ref "C3") (pin "1") (pinfunction "-_1") (pintype "passive"))
      (node (ref "C30") (pin "2") (pinfunction "2_2") (pintype "passive"))
      (node (ref "C31") (pin "2") (pinfunction "2_2") (pintype "passive"))
      (node (ref "C32") (pin "2") (pinfunction "2_2") (pintype "passive"))
      (node (ref "C33") (pin "2") (pinfunction "2_2") (pintype "passive"))
      (node (ref "C34") (pin "2") (pinfunction "2_2") (pintype "passive"))
      (node (ref "C4") (pin "2") (pinfunction "2_2") (pintype "passive"))
      (node (ref "C5") (pin "2") (pinfunction "2_2") (pintype "passive"))
      (node (ref "C6") (pin "1") (pinfunction "1_1") (pintype "passive"))
      (node (ref "C9") (pin "2") (pinfunction "2_2") (pintype "passive"))
      (node (ref "D10") (pin "3") (pinfunction "COM_3") (pintype "power_in"))
      (node (ref "D2") (pin "2") (pinfunction "A_2") (pintype "passive"))
      (node (ref "D3") (pin "A") (pinfunction "A_A") (pintype "passive"))
      (node (ref "D4") (pin "3") (pinfunction "COM_3") (pintype "power_in"))
      (node (ref "D5") (pin "3") (pinfunction "COM_3") (pintype "power_in"))
      (node (ref "D6") (pin "1") (pinfunction "P$1_1") (pintype "bidirectional"))
      (node (ref "D7") (pin "1") (pinfunction "P$1_1") (pintype "bidirectional"))
      (node (ref "D8") (pin "3") (pinfunction "COM_3") (pintype "power_in"))
      (node (ref "D9") (pin "3") (pinfunction "COM_3") (pintype "power_in"))
      (node (ref "IC1") (pin "1") (pinfunction "ADJ_1") (pintype "input"))
      (node (ref "IC2") (pin "1") (pinfunction "ADJ_1") (pintype "input"))
      (node (ref "IC3") (pin "2") (pinfunction "GND_2") (pintype "bidirectional"))
      (node (ref "IC3") (pin "5") (pinfunction "GND_5") (pintype "bidirectional"))
      (node (ref "IC5") (pin "11") (pinfunction "VSSA_11") (pintype "bidirectional"))
      (node (ref "IC5") (pin "15") (pinfunction "VREFN_15") (pintype "bidirectional"))
      (node (ref "IC5") (pin "31") (pinfunction "VSS_31") (pintype "bidirectional"))
      (node (ref "IC5") (pin "41") (pinfunction "VSS_41") (pintype "bidirectional"))
      (node (ref "IC5") (pin "55") (pinfunction "VSS_55") (pintype "bidirectional"))
      (node (ref "IC5") (pin "72") (pinfunction "VSS_72") (pintype "bidirectional"))
      (node (ref "IC5") (pin "83") (pinfunction "VSS_83") (pintype "bidirectional"))
      (node (ref "IC5") (pin "97") (pinfunction "VSS_97") (pintype "bidirectional"))
      (node (ref "IC6") (pin "1") (pinfunction "GND_1") (pintype "bidirectional"))
      (node (ref "IC6") (pin "12") (pinfunction "GND1_12") (pintype "bidirectional"))
      (node (ref "IC6") (pin "25") (pinfunction "GND2_25") (pintype "bidirectional"))
      (node (ref "IC6") (pin "27") (pinfunction "GND3_27") (pintype "bidirectional"))
      (node (ref "IC6") (pin "28") (pinfunction "GND4_28") (pintype "bidirectional"))
      (node (ref "IC6") (pin "29") (pinfunction "GND5_29") (pintype "bidirectional"))
      (node (ref "IC7") (pin "4") (pinfunction "GND_4") (pintype "bidirectional"))
      (node (ref "IC7") (pin "PAD") (pinfunction "PAD_PAD") (pintype "bidirectional"))
      (node (ref "J1") (pin "5") (pinfunction "GND_5") (pintype "bidirectional"))
      (node (ref "J1") (pin "S1") (pinfunction "P$1_S1") (pintype "bidirectional"))
      (node (ref "J1") (pin "S2") (pinfunction "P$2_S2") (pintype "bidirectional"))
      (node (ref "J2") (pin "4") (pinfunction "4_4") (pintype "passive"))
      (node (ref "J2") (pin "5") (pinfunction "5_5") (pintype "passive"))
      (node (ref "J3") (pin "6") (pinfunction "GND_6") (pintype "passive"))
      (node (ref "J4") (pin "1") (pinfunction "1_1") (pintype "passive"))
      (node (ref "J5") (pin "3") (pinfunction "3_3") (pintype "passive"))
      (node (ref "J5") (pin "5") (pinfunction "5_5") (pintype "passive"))
      (node (ref "J5") (pin "9") (pinfunction "9_9") (pintype "passive"))
      (node (ref "JP2") (pin "2") (pinfunction "2_2") (pintype "passive"))
      (node (ref "LED1") (pin "2") (pinfunction "C_2") (pintype "bidirectional"))
      (node (ref "LED4") (pin "2") (pinfunction "C_2") (pintype "bidirectional"))
      (node (ref "R11") (pin "1") (pinfunction "1_1") (pintype "passive"))
      (node (ref "R17") (pin "2") (pinfunction "2_2") (pintype "passive"))
      (node (ref "R18") (pin "2") (pinfunction "2_2") (pintype "passive"))
      (node (ref "R25") (pin "1") (pinfunction "1_1") (pintype "passive"))
      (node (ref "R25B") (pin "P$1") (pinfunction "1_P$1") (pintype "passive"))
      (node (ref "S1") (pin "P$1") (pinfunction "1_P$1") (pintype "passive"))
      (node (ref "S2") (pin "P$1") (pinfunction "1_P$1") (pintype "passive"))
    )
    (net (code "38") (name "Net-(C1-Pad2)") (class "Default")
      (node (ref "C1") (pin "2") (pinfunction "2_2") (pintype "passive"))
      (node (ref "C5") (pin "1") (pinfunction "1_1") (pintype "passive"))
    )
    (net (code "39") (name "Net-(C3-+)") (class "Default")
      (node (ref "C1") (pin "1") (pinfunction "1_1") (pintype "passive"))
      (node (ref "C3") (pin "2") (pinfunction "+_2") (pintype "passive"))
      (node (ref "D1") (pin "C") (pinfunction "C_C") (pintype "passive"))
      (node (ref "IC1") (pin "3") (pinfunction "IN_3") (pintype "input"))
    )
    (net (code "40") (name "Net-(C12-Pad1)") (class "Default")
      (node (ref "C12") (pin "1") (pinfunction "1_1") (pintype "passive"))
      (node (ref "C7") (pin "2") (pinfunction "2_2") (pintype "passive"))
    )
    (net (code "41") (name "Net-(C13-Pad1)") (class "Default")
      (node (ref "C13") (pin "1") (pinfunction "1_1") (pintype "passive"))
      (node (ref "C8") (pin "2") (pinfunction "2_2") (pintype "passive"))
    )
    (net (code "42") (name "Net-(D6-P$2)") (class "Default")
      (node (ref "D6") (pin "2") (pinfunction "P$2_2") (pintype "bidirectional"))
      (node (ref "J1") (pin "3") (pinfunction "D+_3") (pintype "bidirectional"))
      (node (ref "R7") (pin "2") (pinfunction "2_2") (pintype "passive"))
      (node (ref "R8") (pin "1") (pinfunction "1_1") (pintype "passive"))
    )
    (net (code "43") (name "Net-(D7-P$2)") (class "Default")
      (node (ref "D7") (pin "2") (pinfunction "P$2_2") (pintype "bidirectional"))
      (node (ref "J1") (pin "2") (pinfunction "D-_2") (pintype "bidirectional"))
      (node (ref "R10") (pin "2") (pinfunction "2_2") (pintype "passive"))
    )
    (net (code "44") (name "Net-(IC5A-RTCX1)") (class "Default")
      (node (ref "C24") (pin "2") (pinfunction "2_2") (pintype "passive"))
      (node (ref "IC5") (pin "16") (pinfunction "RTCX1_16") (pintype "bidirectional"))
      (node (ref "Q2") (pin "2") (pinfunction "2_2") (pintype "passive"))
    )
    (net (code "45") (name "Net-(IC5A-RTCX2)") (class "Default")
      (node (ref "C25") (pin "2") (pinfunction "2_2") (pintype "passive"))
      (node (ref "IC5") (pin "18") (pinfunction "RTCX2_18") (pintype "bidirectional"))
      (node (ref "Q2") (pin "1") (pinfunction "1_1") (pintype "passive"))
    )
    (net (code "46") (name "Net-(IC5A-X1)") (class "Default")
      (node (ref "C26") (pin "1") (pinfunction "1_1") (pintype "passive"))
      (node (ref "IC5") (pin "22") (pinfunction "X1_22") (pintype "bidirectional"))
      (node (ref "Q3") (pin "3") (pinfunction "2_3") (pintype "passive"))
    )
    (net (code "47") (name "Net-(IC5A-X2)") (class "Default")
      (node (ref "C28") (pin "1") (pinfunction "1_1") (pintype "passive"))
      (node (ref "IC5") (pin "23") (pinfunction "X2_23") (pintype "bidirectional"))
      (node (ref "Q3") (pin "1") (pinfunction "1_1") (pintype "passive"))
    )
    (net (code "48") (name "Net-(IC5C-P1.18{slash}USB_UP{slash}PWM1.1{slash}CAP1.0)") (class "Default")
      (node (ref "IC5") (pin "32") (pinfunction "P1.18/USB_UP/PWM1.1/CAP1.0_32") (pintype "bidirectional"))
      (node (ref "R4") (pin "1") (pinfunction "1_1") (pintype "passive"))
    )
    (net (code "49") (name "Net-(IC5C-P1.20{slash}MCFB0{slash}PWM1.2{slash}SCK0)") (class "Default")
      (node (ref "IC5") (pin "34") (pinfunction "P1.20/MCFB0/PWM1.2/SCK0_34") (pintype "bidirectional"))
      (node (ref "R6") (pin "1") (pinfunction "1_1") (pintype "passive"))
    )
    (net (code "50") (name "Net-(IC5C-P1.21{slash}~{MCABORT}{slash}PWM1.3{slash}SSEL0)") (class "Default")
      (node (ref "IC5") (pin "35") (pinfunction "P1.21/~{MCABORT}/PWM1.3/SSEL0_35") (pintype "bidirectional"))
      (node (ref "R5") (pin "1") (pinfunction "1_1") (pintype "passive"))
    )
    (net (code "51") (name "Net-(IC5C-P1.23{slash}MCFB1{slash}PWM1.4{slash}MISO0)") (class "Default")
      (node (ref "IC5") (pin "37") (pinfunction "P1.23/MCFB1/PWM1.4/MISO0_37") (pintype "bidirectional"))
      (node (ref "R22") (pin "1") (pinfunction "1_1") (pintype "passive"))
    )
    (net (code "52") (name "Net-(IC5C-P1.24{slash}MCFB2{slash}PWM1.5{slash}MOSI0)") (class "Default")
      (node (ref "IC5") (pin "38") (pinfunction "P1.24/MCFB2/PWM1.5/MOSI0_38") (pintype "bidirectional"))
      (node (ref "R21") (pin "1") (pinfunction "1_1") (pintype "passive"))
    )
    (net (code "53") (name "Net-(IC5C-P1.26{slash}MC1B{slash}PWM1.6{slash}CAP0.0)") (class "Default")
      (node (ref "IC5") (pin "40") (pinfunction "P1.26/MC1B/PWM1.6/CAP0.0_40") (pintype "bidirectional"))
      (node (ref "R20") (pin "1") (pinfunction "1_1") (pintype "passive"))
    )
    (net (code "54") (name "Net-(IC5D-P2.13{slash}~{EINT3}{slash}I2STX_SDA)") (class "Default")
      (node (ref "IC5") (pin "50") (pinfunction "P2.13/~{EINT3}/I2STX_SDA_50") (pintype "bidirectional"))
      (node (ref "IC7") (pin "2") (pinfunction "~{EN}_2") (pintype "bidirectional"))
      (node (ref "TP14") (pin "P$1") (pinfunction "1_P$1") (pintype "bidirectional"))
    )
    (net (code "55") (name "Net-(IC6-PIO5)") (class "Default")
      (node (ref "IC6") (pin "21") (pinfunction "PIO5_21") (pintype "bidirectional"))
      (node (ref "LED3") (pin "C") (pinfunction "C_C") (pintype "passive"))
    )
    (net (code "56") (name "Net-(IC6-RESET)") (class "Default")
      (node (ref "IC6") (pin "5") (pinfunction "RESET_5") (pintype "bidirectional"))
      (node (ref "SJ6") (pin "2") (pinfunction "2_2") (pintype "passive"))
    )
    (net (code "57") (name "Net-(IC6-VDD)") (class "Default")
      (node (ref "C21") (pin "2") (pinfunction "2_2") (pintype "passive"))
      (node (ref "C22") (pin "2") (pinfunction "2_2") (pintype "passive"))
      (node (ref "FB1") (pin "1") (pinfunction "1_1") (pintype "passive"))
      (node (ref "IC6") (pin "11") (pinfunction "VDD_11") (pintype "bidirectional"))
    )
    (net (code "58") (name "Net-(IC7-CT)") (class "Default")
      (node (ref "C27") (pin "1") (pinfunction "1_1") (pintype "passive"))
      (node (ref "IC7") (pin "6") (pinfunction "CT_6") (pintype "bidirectional"))
    )
    (net (code "59") (name "Net-(IC7-ISET)") (class "Default")
      (node (ref "IC7") (pin "5") (pinfunction "ISET_5") (pintype "bidirectional"))
      (node (ref "R18") (pin "1") (pinfunction "1_1") (pintype "passive"))
    )
    (net (code "60") (name "Net-(IC7-VOUT)") (class "Default")
      (node (ref "IC7") (pin "7") (pinfunction "VOUT_7") (pintype "bidirectional"))
      (node (ref "J4") (pin "2") (pinfunction "2_2") (pintype "passive"))
      (node (ref "TP15") (pin "P$1") (pinfunction "1_P$1") (pintype "bidirectional"))
    )
    (net (code "61") (name "Net-(IC7-~{FLT})") (class "Default")
      (node (ref "IC7") (pin "1") (pinfunction "~{FLT}_1") (pintype "bidirectional"))
      (node (ref "TP22") (pin "P$1") (pinfunction "1_P$1") (pintype "bidirectional"))
    )
    (net (code "62") (name "Net-(IC7-~{PG})") (class "Default")
      (node (ref "IC7") (pin "8") (pinfunction "~{PG}_8") (pintype "bidirectional"))
      (node (ref "TP23") (pin "P$1") (pinfunction "1_P$1") (pintype "bidirectional"))
    )
    (net (code "63") (name "Net-(J1-ID)") (class "Default")
      (node (ref "J1") (pin "4") (pinfunction "ID_4") (pintype "bidirectional"))
      (node (ref "R25") (pin "2") (pinfunction "2_2") (pintype "passive"))
      (node (ref "R25B") (pin "P$2") (pinfunction "2_P$2") (pintype "passive"))
    )
    (net (code "64") (name "Net-(J3-DTR)") (class "Default")
      (node (ref "J3") (pin "1") (pinfunction "DTR_1") (pintype "passive"))
      (node (ref "SJ5") (pin "2") (pinfunction "2_2") (pintype "passive"))
    )
    (net (code "65") (name "Net-(LED1-B)") (class "Default")
      (node (ref "LED1") (pin "3") (pinfunction "B_3") (pintype "bidirectional"))
      (node (ref "R21") (pin "2") (pinfunction "2_2") (pintype "passive"))
    )
    (net (code "66") (name "Net-(LED1-G)") (class "Default")
      (node (ref "LED1") (pin "4") (pinfunction "G_4") (pintype "bidirectional"))
      (node (ref "R22") (pin "2") (pinfunction "2_2") (pintype "passive"))
    )
    (net (code "67") (name "Net-(LED1-R)") (class "Default")
      (node (ref "LED1") (pin "1") (pinfunction "R_1") (pintype "bidirectional"))
      (node (ref "R20") (pin "2") (pinfunction "2_2") (pintype "passive"))
    )
    (net (code "68") (name "Net-(LED2-PadC)") (class "Default")
      (node (ref "LED2") (pin "C") (pinfunction "C_C") (pintype "passive"))
      (node (ref "R11") (pin "2") (pinfunction "2_2") (pintype "passive"))
    )
    (net (code "69") (name "Net-(LED3-PadA)") (class "Default")
      (node (ref "LED3") (pin "A") (pinfunction "A_A") (pintype "passive"))
      (node (ref "R19") (pin "2") (pinfunction "2_2") (pintype "passive"))
    )
    (net (code "70") (name "Net-(LED4-B)") (class "Default")
      (node (ref "LED4") (pin "3") (pinfunction "B_3") (pintype "bidirectional"))
      (node (ref "R6") (pin "2") (pinfunction "2_2") (pintype "passive"))
    )
    (net (code "71") (name "Net-(LED4-G)") (class "Default")
      (node (ref "LED4") (pin "4") (pinfunction "G_4") (pintype "bidirectional"))
      (node (ref "R4") (pin "2") (pinfunction "2_2") (pintype "passive"))
    )
    (net (code "72") (name "Net-(LED4-R)") (class "Default")
      (node (ref "LED4") (pin "1") (pinfunction "R_1") (pintype "bidirectional"))
      (node (ref "R5") (pin "2") (pinfunction "2_2") (pintype "passive"))
    )
    (net (code "73") (name "Net-(Q1-B)") (class "Default")
      (node (ref "Q1") (pin "1") (pinfunction "B_1") (pintype "passive"))
      (node (ref "R3") (pin "1") (pinfunction "1_1") (pintype "passive"))
      (node (ref "R9") (pin "1") (pinfunction "1_1") (pintype "passive"))
    )
    (net (code "74") (name "Net-(Q1-E)") (class "Default")
      (node (ref "LED2") (pin "A") (pinfunction "A_A") (pintype "passive"))
      (node (ref "Q1") (pin "2") (pinfunction "E_2") (pintype "passive"))
      (node (ref "R8") (pin "2") (pinfunction "2_2") (pintype "passive"))
    )
    (net (code "75") (name "Net-(R1-Pad2)") (class "Default")
      (node (ref "R1") (pin "2") (pinfunction "2_2") (pintype "passive"))
      (node (ref "SJ1") (pin "2") (pinfunction "2_2") (pintype "passive"))
    )
    (net (code "76") (name "Net-(R2-Pad1)") (class "Default")
      (node (ref "R2") (pin "1") (pinfunction "1_1") (pintype "passive"))
      (node (ref "SJ2") (pin "1") (pinfunction "1_1") (pintype "passive"))
    )
    (net (code "77") (name "unconnected-(IC5A-~{RSTOUT}-Pad14)") (class "Default")
      (node (ref "IC5") (pin "14") (pinfunction "~{RSTOUT}_14") (pintype "bidirectional"))
    )
    (net (code "78") (name "unconnected-(IC5B-P0.0{slash}CAN_RX1{slash}TXD3{slash}SDA1-Pad46)") (class "Default")
      (node (ref "IC5") (pin "46") (pinfunction "P0.0/CAN_RX1/TXD3/SDA1_46") (pintype "bidirectional"))
    )
    (net (code "79") (name "unconnected-(IC5B-P0.1{slash}CAN_TX1{slash}RXD3{slash}SCL1-Pad47)") (class "Default")
      (node (ref "IC5") (pin "47") (pinfunction "P0.1/CAN_TX1/RXD3/SCL1_47") (pintype "bidirectional"))
    )
    (net (code "80") (name "unconnected-(IC5B-P0.7{slash}I2STX_CLK{slash}SCK1{slash}MAT2.1-Pad78)") (class "Default")
      (node (ref "IC5") (pin "78") (pinfunction "P0.7/I2STX_CLK/SCK1/MAT2.1_78") (pintype "bidirectional"))
    )
    (net (code "81") (name "unconnected-(IC5B-P0.8{slash}I2STX_WS{slash}MISO1{slash}MAT2.2-Pad77)") (class "Default")
      (node (ref "IC5") (pin "77") (pinfunction "P0.8/I2STX_WS/MISO1/MAT2.2_77") (pintype "bidirectional"))
    )
    (net (code "82") (name "unconnected-(IC5B-P0.9{slash}I2STX_SDA{slash}MOSI1{slash}MAT2.3-Pad76)") (class "Default")
      (node (ref "IC5") (pin "76") (pinfunction "P0.9/I2STX_SDA/MOSI1/MAT2.3_76") (pintype "bidirectional"))
    )
    (net (code "83") (name "unconnected-(IC5B-P0.10{slash}TXD2{slash}SDA2{slash}MAT3.0-Pad48)") (class "Default")
      (node (ref "IC5") (pin "48") (pinfunction "P0.10/TXD2/SDA2/MAT3.0_48") (pintype "bidirectional"))
    )
    (net (code "84") (name "unconnected-(IC5B-P0.11{slash}RXD2{slash}SCL2{slash}MAT3.1-Pad49)") (class "Default")
      (node (ref "IC5") (pin "49") (pinfunction "P0.11/RXD2/SCL2/MAT3.1_49") (pintype "bidirectional"))
    )
    (net (code "85") (name "unconnected-(IC5B-P0.20{slash}DTR1{slash}SCL1-Pad58)") (class "Default")
      (node (ref "IC5") (pin "58") (pinfunction "P0.20/DTR1/SCL1_58") (pintype "bidirectional"))
    )
    (net (code "86") (name "unconnected-(IC5B-P0.23{slash}AD0.0{slash}I2SRX_CLK{slash}CAP3.0-Pad9)") (class "Default")
      (node (ref "IC5") (pin "9") (pinfunction "P0.23/AD0.0/I2SRX_CLK/CAP3.0_9") (pintype "bidirectional"))
    )
    (net (code "87") (name "unconnected-(IC5B-P0.24{slash}AD0.1{slash}I2SRX_WS{slash}CAP3.1-Pad8)") (class "Default")
      (node (ref "IC5") (pin "8") (pinfunction "P0.24/AD0.1/I2SRX_WS/CAP3.1_8") (pintype "bidirectional"))
    )
    (net (code "88") (name "unconnected-(IC5B-P0.25{slash}AD9.2{slash}I2SRX_SDA{slash}TXD3-Pad7)") (class "Default")
      (node (ref "IC5") (pin "7") (pinfunction "P0.25/AD9.2/I2SRX_SDA/TXD3_7") (pintype "bidirectional"))
    )
    (net (code "89") (name "unconnected-(IC5B-P0.26{slash}AD0.3{slash}AOUT{slash}RXD3-Pad6)") (class "Default")
      (node (ref "IC5") (pin "6") (pinfunction "P0.26/AD0.3/AOUT/RXD3_6") (pintype "bidirectional"))
    )
    (net (code "90") (name "unconnected-(IC5B-P0.27{slash}SDA0{slash}USB_SDA-Pad25)") (class "Default")
      (node (ref "IC5") (pin "25") (pinfunction "P0.27/SDA0/USB_SDA_25") (pintype "bidirectional"))
    )
    (net (code "91") (name "unconnected-(IC5B-P0.28{slash}SCL0{slash}USB_SCL-Pad24)") (class "Default")
      (node (ref "IC5") (pin "24") (pinfunction "P0.28/SCL0/USB_SCL_24") (pintype "bidirectional"))
    )
    (net (code "92") (name "unconnected-(IC5C-P1.0{slash}ENET-TXD0-Pad95)") (class "Default")
      (node (ref "IC5") (pin "95") (pinfunction "P1.0/ENET-TXD0_95") (pintype "bidirectional"))
    )
    (net (code "93") (name "unconnected-(IC5C-P1.1{slash}ENET-TXD1-Pad94)") (class "Default")
      (node (ref "IC5") (pin "94") (pinfunction "P1.1/ENET-TXD1_94") (pintype "bidirectional"))
    )
    (net (code "94") (name "unconnected-(IC5C-P1.4{slash}ENET-TX_EN-Pad93)") (class "Default")
      (node (ref "IC5") (pin "93") (pinfunction "P1.4/ENET-TX_EN_93") (pintype "bidirectional"))
    )
    (net (code "95") (name "unconnected-(IC5C-P1.8{slash}ENET_CRS-Pad92)") (class "Default")
      (node (ref "IC5") (pin "92") (pinfunction "P1.8/ENET_CRS_92") (pintype "bidirectional"))
    )
    (net (code "96") (name "unconnected-(IC5C-P1.9{slash}ENET_RXD0-Pad91)") (class "Default")
      (node (ref "IC5") (pin "91") (pinfunction "P1.9/ENET_RXD0_91") (pintype "bidirectional"))
    )
    (net (code "97") (name "unconnected-(IC5C-P1.10{slash}ENET_RXD1-Pad90)") (class "Default")
      (node (ref "IC5") (pin "90") (pinfunction "P1.10/ENET_RXD1_90") (pintype "bidirectional"))
    )
    (net (code "98") (name "unconnected-(IC5C-P1.14{slash}ENET-RX_ER-Pad89)") (class "Default")
      (node (ref "IC5") (pin "89") (pinfunction "P1.14/ENET-RX_ER_89") (pintype "bidirectional"))
    )
    (net (code "99") (name "unconnected-(IC5C-P1.15{slash}ENET-RX_CLK-Pad88)") (class "Default")
      (node (ref "IC5") (pin "88") (pinfunction "P1.15/ENET-RX_CLK_88") (pintype "bidirectional"))
    )
    (net (code "100") (name "unconnected-(IC5C-P1.16{slash}ENET-MDC-Pad87)") (class "Default")
      (node (ref "IC5") (pin "87") (pinfunction "P1.16/ENET-MDC_87") (pintype "bidirectional"))
    )
    (net (code "101") (name "unconnected-(IC5C-P1.17{slash}ENET-MDIO-Pad86)") (class "Default")
      (node (ref "IC5") (pin "86") (pinfunction "P1.17/ENET-MDIO_86") (pintype "bidirectional"))
    )
    (net (code "102") (name "unconnected-(IC5C-P1.19{slash}MC0A{slash}~{USB_PPWR}{slash}CAP1.1-Pad33)") (class "Default")
      (node (ref "IC5") (pin "33") (pinfunction "P1.19/MC0A/~{USB_PPWR}/CAP1.1_33") (pintype "bidirectional"))
    )
    (net (code "103") (name "unconnected-(IC5C-P1.22{slash}MC0B{slash}USB_PWRD{slash}MAT1.0-Pad36)") (class "Default")
      (node (ref "IC5") (pin "36") (pinfunction "P1.22/MC0B/USB_PWRD/MAT1.0_36") (pintype "bidirectional"))
    )
    (net (code "104") (name "unconnected-(IC5C-P1.25{slash}MC1A{slash}MAT1.1-Pad39)") (class "Default")
      (node (ref "IC5") (pin "39") (pinfunction "P1.25/MC1A/MAT1.1_39") (pintype "bidirectional"))
    )
    (net (code "105") (name "unconnected-(IC5C-P1.27{slash}CLKOUT{slash}~{USB_OVRCR}{slash}CAP0.1-Pad43)") (class "Default")
      (node (ref "IC5") (pin "43") (pinfunction "P1.27/CLKOUT/~{USB_OVRCR}/CAP0.1_43") (pintype "bidirectional"))
    )
    (net (code "106") (name "unconnected-(IC5C-P1.28{slash}MC2A{slash}PCAP1.0{slash}MAT0.0-Pad44)") (class "Default")
      (node (ref "IC5") (pin "44") (pinfunction "P1.28/MC2A/PCAP1.0/MAT0.0_44") (pintype "bidirectional"))
    )
    (net (code "107") (name "unconnected-(IC5C-P1.29{slash}MC2B{slash}PCAP1.1{slash}MAT0.1-Pad45)") (class "Default")
      (node (ref "IC5") (pin "45") (pinfunction "P1.29/MC2B/PCAP1.1/MAT0.1_45") (pintype "bidirectional"))
    )
    (net (code "108") (name "unconnected-(IC5C-P1.31{slash}SCK1{slash}AD0.5-Pad20)") (class "Default")
      (node (ref "IC5") (pin "20") (pinfunction "P1.31/SCK1/AD0.5_20") (pintype "bidirectional"))
    )
    (net (code "109") (name "unconnected-(IC5D-P2.0{slash}PWM1.1{slash}TXD1{slash}TRACECLK-Pad75)") (class "Default")
      (node (ref "IC5") (pin "75") (pinfunction "P2.0/PWM1.1/TXD1/TRACECLK_75") (pintype "bidirectional"))
    )
    (net (code "110") (name "unconnected-(IC5D-P2.1{slash}PWM1.2{slash}RXD1-Pad74)") (class "Default")
      (node (ref "IC5") (pin "74") (pinfunction "P2.1/PWM1.2/RXD1_74") (pintype "bidirectional"))
    )
    (net (code "111") (name "unconnected-(IC5D-P2.3{slash}PWM1.4{slash}DCD1{slash}TRACEDATA2-Pad70)") (class "Default")
      (node (ref "IC5") (pin "70") (pinfunction "P2.3/PWM1.4/DCD1/TRACEDATA2_70") (pintype "bidirectional"))
    )
    (net (code "112") (name "unconnected-(IC5D-P2.4{slash}PWM1.5{slash}DSR1{slash}TRACEDATA1-Pad69)") (class "Default")
      (node (ref "IC5") (pin "69") (pinfunction "P2.4/PWM1.5/DSR1/TRACEDATA1_69") (pintype "bidirectional"))
    )
    (net (code "113") (name "unconnected-(IC5D-P2.5{slash}PWM1.6{slash}DTR1{slash}TRACEDATA0-Pad68)") (class "Default")
      (node (ref "IC5") (pin "68") (pinfunction "P2.5/PWM1.6/DTR1/TRACEDATA0_68") (pintype "bidirectional"))
    )
    (net (code "114") (name "unconnected-(IC5D-P2.6{slash}PCAP1.0{slash}RI1{slash}TRACECLK-Pad67)") (class "Default")
      (node (ref "IC5") (pin "67") (pinfunction "P2.6/PCAP1.0/RI1/TRACECLK_67") (pintype "bidirectional"))
    )
    (net (code "115") (name "unconnected-(IC5D-P2.8{slash}CAN_TX2{slash}TXD2-Pad65)") (class "Default")
      (node (ref "IC5") (pin "65") (pinfunction "P2.8/CAN_TX2/TXD2_65") (pintype "bidirectional"))
    )
    (net (code "116") (name "unconnected-(IC5D-P2.11{slash}~{EINT1}{slash}I2STX_CLK-Pad52)") (class "Default")
      (node (ref "IC5") (pin "52") (pinfunction "P2.11/~{EINT1}/I2STX_CLK_52") (pintype "bidirectional"))
    )
    (net (code "117") (name "unconnected-(IC5E-P3.25{slash}MAT0.0{slash}PWM1.2-Pad27)") (class "Default")
      (node (ref "IC5") (pin "27") (pinfunction "P3.25/MAT0.0/PWM1.2_27") (pintype "bidirectional"))
    )
    (net (code "118") (name "unconnected-(IC5E-P3.26{slash}STCLK{slash}MAT0.1{slash}PWM1.3-Pad26)") (class "Default")
      (node (ref "IC5") (pin "26") (pinfunction "P3.26/STCLK/MAT0.1/PWM1.3_26") (pintype "bidirectional"))
    )
    (net (code "119") (name "unconnected-(IC5E-P4.28{slash}RX_MCLK{slash}MAT2.0{slash}TXD3-Pad82)") (class "Default")
      (node (ref "IC5") (pin "82") (pinfunction "P4.28/RX_MCLK/MAT2.0/TXD3_82") (pintype "bidirectional"))
    )
    (net (code "120") (name "unconnected-(IC5E-P4.29{slash}TX_MCLK{slash}MAT2.1{slash}RXD3-Pad85)") (class "Default")
      (node (ref "IC5") (pin "85") (pinfunction "P4.29/TX_MCLK/MAT2.1/RXD3_85") (pintype "bidirectional"))
    )
    (net (code "121") (name "unconnected-(IC5F-NC{slash}VDD3.3V-Pad13)") (class "Default")
      (node (ref "IC5") (pin "13") (pinfunction "NC/VDD3.3V_13") (pintype "bidirectional"))
    )
    (net (code "122") (name "unconnected-(IC5F-VBAT-Pad19)") (class "Default")
      (node (ref "IC5") (pin "19") (pinfunction "VBAT_19") (pintype "bidirectional"))
    )
    (net (code "123") (name "unconnected-(IC6-AIO1-Pad35)") (class "Default")
      (node (ref "IC6") (pin "35") (pinfunction "AIO1_35") (pintype "bidirectional"))
    )
    (net (code "124") (name "unconnected-(IC6-AIO2-Pad30)") (class "Default")
      (node (ref "IC6") (pin "30") (pinfunction "AIO2_30") (pintype "bidirectional"))
    )
    (net (code "125") (name "unconnected-(IC6-NC-Pad26)") (class "Default")
      (node (ref "IC6") (pin "26") (pinfunction "NC_26") (pintype "bidirectional"))
    )
    (net (code "126") (name "unconnected-(IC6-PCMCLK-Pad7)") (class "Default")
      (node (ref "IC6") (pin "7") (pinfunction "PCMCLK_7") (pintype "bidirectional"))
    )
    (net (code "127") (name "unconnected-(IC6-PCMIN-Pad9)") (class "Default")
      (node (ref "IC6") (pin "9") (pinfunction "PCMIN_9") (pintype "bidirectional"))
    )
    (net (code "128") (name "unconnected-(IC6-PCMOUT-Pad10)") (class "Default")
      (node (ref "IC6") (pin "10") (pinfunction "PCMOUT_10") (pintype "bidirectional"))
    )
    (net (code "129") (name "unconnected-(IC6-PCMSYNC-Pad8)") (class "Default")
      (node (ref "IC6") (pin "8") (pinfunction "PCMSYNC_8") (pintype "bidirectional"))
    )
    (net (code "130") (name "unconnected-(IC6-PIO3-Pad20)") (class "Default")
      (node (ref "IC6") (pin "20") (pinfunction "PIO3_20") (pintype "bidirectional"))
    )
    (net (code "131") (name "unconnected-(IC6-PIO4-Pad22)") (class "Default")
      (node (ref "IC6") (pin "22") (pinfunction "PIO4_22") (pintype "bidirectional"))
    )
    (net (code "132") (name "unconnected-(IC6-PIO6-Pad3)") (class "Default")
      (node (ref "IC6") (pin "3") (pinfunction "PIO6_3") (pintype "bidirectional"))
    )
    (net (code "133") (name "unconnected-(IC6-PIO7-Pad4)") (class "Default")
      (node (ref "IC6") (pin "4") (pinfunction "PIO7_4") (pintype "bidirectional"))
    )
    (net (code "134") (name "unconnected-(IC6-PIO8-Pad31)") (class "Default")
      (node (ref "IC6") (pin "31") (pinfunction "PIO8_31") (pintype "bidirectional"))
    )
    (net (code "135") (name "unconnected-(IC6-PIO9-Pad32)") (class "Default")
      (node (ref "IC6") (pin "32") (pinfunction "PIO9_32") (pintype "bidirectional"))
    )
    (net (code "136") (name "unconnected-(IC6-PIO10-Pad33)") (class "Default")
      (node (ref "IC6") (pin "33") (pinfunction "PIO10_33") (pintype "bidirectional"))
    )
    (net (code "137") (name "unconnected-(IC6-PIO11-Pad34)") (class "Default")
      (node (ref "IC6") (pin "34") (pinfunction "PIO11_34") (pintype "bidirectional"))
    )
    (net (code "138") (name "unconnected-(IC6-SPICLK-Pad6)") (class "Default")
      (node (ref "IC6") (pin "6") (pinfunction "SPICLK_6") (pintype "bidirectional"))
    )
    (net (code "139") (name "unconnected-(IC6-SPICSB-Pad23)") (class "Default")
      (node (ref "IC6") (pin "23") (pinfunction "SPICSB_23") (pintype "bidirectional"))
    )
    (net (code "140") (name "unconnected-(IC6-SPIMISO-Pad24)") (class "Default")
      (node (ref "IC6") (pin "24") (pinfunction "SPIMISO_24") (pintype "bidirectional"))
    )
    (net (code "141") (name "unconnected-(IC6-SPIMOSI-Pad2)") (class "Default")
      (node (ref "IC6") (pin "2") (pinfunction "SPIMOSI_2") (pintype "bidirectional"))
    )
    (net (code "142") (name "unconnected-(IC6-USBD+-Pad17)") (class "Default")
      (node (ref "IC6") (pin "17") (pinfunction "USBD+_17") (pintype "bidirectional"))
    )
    (net (code "143") (name "unconnected-(IC6-USBD--Pad18)") (class "Default")
      (node (ref "IC6") (pin "18") (pinfunction "USBD-_18") (pintype "bidirectional"))
    )
    (net (code "144") (name "unconnected-(J2-Pad2)") (class "Default")
      (node (ref "J2") (pin "2") (pinfunction "2_2") (pintype "passive"))
    )
    (net (code "145") (name "unconnected-(J2-Pad7)") (class "Default")
      (node (ref "J2") (pin "7") (pinfunction "7_7") (pintype "passive"))
    )
    (net (code "146") (name "unconnected-(J2-Pad9)") (class "Default")
      (node (ref "J2") (pin "9") (pinfunction "9_9") (pintype "passive"))
    )
    (net (code "147") (name "unconnected-(J2-Pad10)") (class "Default")
      (node (ref "J2") (pin "10") (pinfunction "10_10") (pintype "passive"))
    )
    (net (code "148") (name "unconnected-(J2-Pad12)") (class "Default")
      (node (ref "J2") (pin "12") (pinfunction "12_12") (pintype "passive"))
    )
    (net (code "149") (name "unconnected-(J2-Pad13)") (class "Default")
      (node (ref "J2") (pin "13") (pinfunction "13_13") (pintype "passive"))
    )
    (net (code "150") (name "unconnected-(J2-Pad15)") (class "Default")
      (node (ref "J2") (pin "15") (pinfunction "15_15") (pintype "passive"))
    )
    (net (code "151") (name "unconnected-(J3-CTS-Pad5)") (class "Default")
      (node (ref "J3") (pin "5") (pinfunction "CTS_5") (pintype "passive"))
    )
  )
)
